# NetTieLibSample.net
KiCad netlist of a schematic drawn in Altium Designer
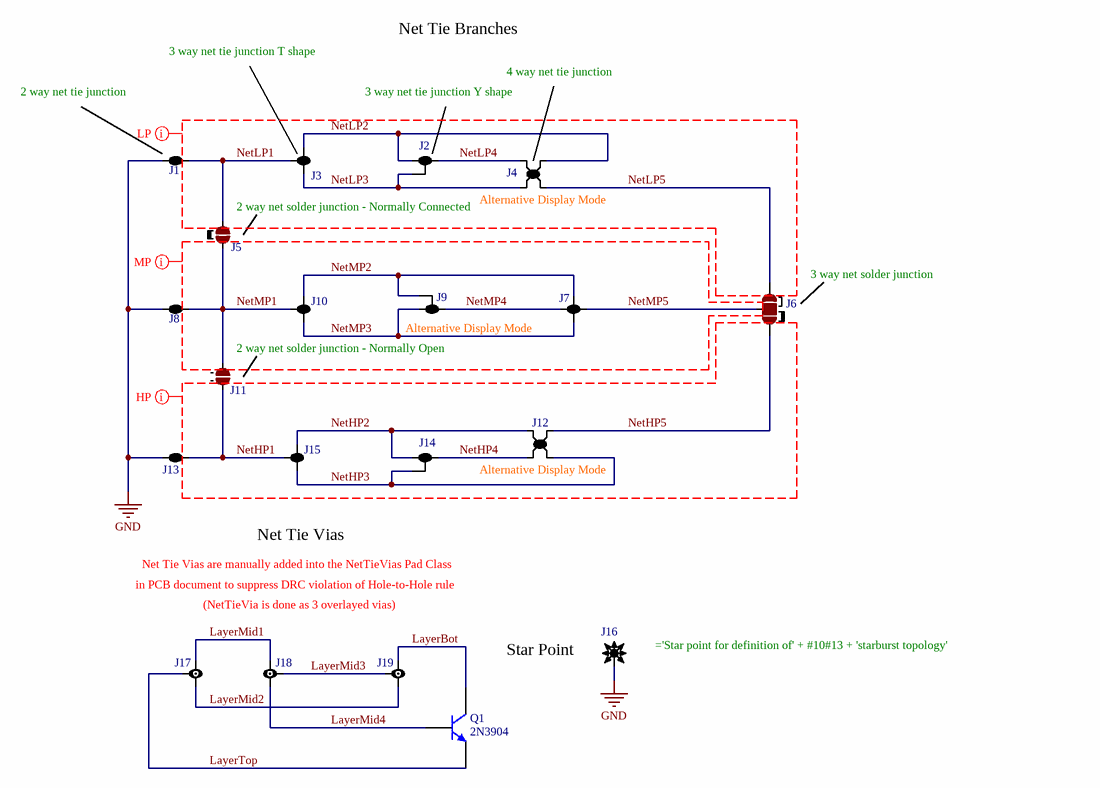
[diagram p0: NetTieLibSample.SchDoc]

(export (version "E")
  (design (tool "Eeschema 10.0.6"))
  (components
    (comp (ref "J1")
      (value "2 way net tie junction")
      (footprint "2way_LP")
      (libsource (lib "NetTieLib") (part "2way"))
    )
    (comp (ref "J2")
      (value "3 way net tie junction Y shape")
      (footprint "3wayY_LP")
      (libsource (lib "NetTieLib") (part "3wayY"))
    )
    (comp (ref "J3")
      (value "3 way net tie junction T shape")
      (footprint "3wayT_LP")
      (libsource (lib "NetTieLib") (part "3wayT"))
    )
    (comp (ref "J4")
      (value "4 way net tie junction")
      (footprint "4way_LP")
      (libsource (lib "NetTieLib") (part "4way"))
    )
    (comp (ref "J5")
      (value "2 way net solder junction - Normally Connected")
      (footprint "2waySolder_NC")
      (libsource (lib "NetTieLib") (part "2waySolderNC"))
    )
    (comp (ref "J6")
      (value "3 way net solder junction")
      (footprint "3waySolder")
      (libsource (lib "NetTieLib") (part "3waySolder"))
    )
    (comp (ref "J7")
      (value "4 way net tie junction")
      (footprint "4way_MP")
      (libsource (lib "") (part "4way_1"))
    )
    (comp (ref "J8")
      (value "2 way net tie junction")
      (footprint "2way_MP")
      (libsource (lib "NetTieLib") (part "2way"))
    )
    (comp (ref "J9")
      (value "3 way net tie junction Y shape")
      (footprint "3wayY_MP")
      (libsource (lib "") (part "3wayY_1"))
    )
    (comp (ref "J10")
      (value "3 way net tie junction T shape")
      (footprint "3wayT_MP")
      (libsource (lib "NetTieLib") (part "3wayT"))
    )
    (comp (ref "J11")
      (value "2 way net solder junction - Normally Open")
      (footprint "2waySolder_NO")
      (libsource (lib "NetTieLib") (part "2waySolderNO"))
    )
    (comp (ref "J12")
      (value "4 way net tie junction")
      (footprint "4way_HP")
      (libsource (lib "NetTieLib") (part "4way"))
    )
    (comp (ref "J13")
      (value "2 way net tie junction")
      (footprint "2way_HP")
      (libsource (lib "NetTieLib") (part "2way"))
    )
    (comp (ref "J14")
      (value "3 way net tie junction Y shape")
      (footprint "3wayY_HP")
      (libsource (lib "NetTieLib") (part "3wayY"))
    )
    (comp (ref "J15")
      (value "3 way net tie junction T shape")
      (footprint "3wayT_HP")
      (libsource (lib "NetTieLib") (part "3wayT"))
    )
    (comp (ref "J16")
      (value "Star point for definition ofstarburst topology")
      (footprint "StarPoint")
      (description "Star point for definition of starburst topology")
      (libsource (lib "NetTieLib") (part "StarPoint"))
    )
    (comp (ref "J17")
      (value "Net Tie Via")
      (footprint "NetTieVia03")
      (libsource (lib "NetTieLib") (part "NetTieVia"))
    )
    (comp (ref "J18")
      (value "Net Tie Via")
      (footprint "NetTieVia06")
      (libsource (lib "") (part "NetTieVia_1"))
    )
    (comp (ref "J19")
      (value "Net Tie Via")
      (footprint "NetTieVia08")
      (libsource (lib "NetTieLib") (part "NetTieVia"))
    )
    (comp (ref "Q1")
      (value "2N3904")
      (footprint "TO-92A")
      (description "NPN General Purpose Amplifier")
      (fields (field (name "PUBLISHER") "Altium Limited"))
      (libsource (lib "Miscellaneous Devices") (part "2N3904"))
    )
  )
  (nets
    (net (code "1") (name "/LayerBot") (class "Default")
      (node (ref "J19") (pin "2") (pinfunction "2_2") (pintype "passive"))
      (node (ref "Q1") (pin "3") (pinfunction "C_3") (pintype "passive"))
    )
    (net (code "2") (name "/LayerMid1") (class "Default")
      (node (ref "J17") (pin "2") (pinfunction "2_2") (pintype "passive"))
      (node (ref "J18") (pin "2") (pinfunction "2_2") (pintype "passive"))
    )
    (net (code "3") (name "/LayerMid2") (class "Default")
      (node (ref "J17") (pin "3") (pinfunction "3_3") (pintype "passive"))
      (node (ref "J19") (pin "3") (pinfunction "3_3") (pintype "passive"))
    )
    (net (code "4") (name "/LayerMid3") (class "Default")
      (node (ref "J18") (pin "1") (pinfunction "1_1") (pintype "passive"))
      (node (ref "J19") (pin "1") (pinfunction "1_1") (pintype "passive"))
    )
    (net (code "5") (name "/LayerMid4") (class "Default")
      (node (ref "J18") (pin "3") (pinfunction "3_3") (pintype "passive"))
      (node (ref "Q1") (pin "2") (pinfunction "B_2") (pintype "passive"))
    )
    (net (code "6") (name "/LayerTop") (class "Default")
      (node (ref "J17") (pin "1") (pinfunction "1_1") (pintype "passive"))
      (node (ref "Q1") (pin "1") (pinfunction "E_1") (pintype "passive"))
    )
    (net (code "7") (name "/NetHP1") (class "Default")
      (node (ref "J11") (pin "2") (pinfunction "2_2") (pintype "passive"))
      (node (ref "J13") (pin "2") (pinfunction "2_2") (pintype "passive"))
      (node (ref "J15") (pin "1") (pinfunction "1_1") (pintype "passive"))
    )
    (net (code "8") (name "/NetHP2") (class "Default")
      (node (ref "J12") (pin "2") (pinfunction "2_2") (pintype "passive"))
      (node (ref "J14") (pin "3") (pinfunction "3_3") (pintype "passive"))
      (node (ref "J15") (pin "2") (pinfunction "2_2") (pintype "passive"))
    )
    (net (code "9") (name "/NetHP3") (class "Default")
      (node (ref "J12") (pin "3") (pinfunction "3_3") (pintype "passive"))
      (node (ref "J14") (pin "2") (pinfunction "2_2") (pintype "passive"))
      (node (ref "J15") (pin "3") (pinfunction "3_3") (pintype "passive"))
    )
    (net (code "10") (name "/NetHP4") (class "Default")
      (node (ref "J12") (pin "1") (pinfunction "1_1") (pintype "passive"))
      (node (ref "J14") (pin "1") (pinfunction "1_1") (pintype "passive"))
    )
    (net (code "11") (name "/NetHP5") (class "Default")
      (node (ref "J12") (pin "4") (pinfunction "4_4") (pintype "passive"))
      (node (ref "J6") (pin "1") (pinfunction "1_1") (pintype "passive"))
    )
    (net (code "12") (name "/NetLP1") (class "Default")
      (node (ref "J1") (pin "2") (pinfunction "2_2") (pintype "passive"))
      (node (ref "J3") (pin "1") (pinfunction "1_1") (pintype "passive"))
      (node (ref "J5") (pin "1") (pinfunction "1_1") (pintype "passive"))
    )
    (net (code "13") (name "/NetLP2") (class "Default")
      (node (ref "J2") (pin "3") (pinfunction "3_3") (pintype "passive"))
      (node (ref "J3") (pin "2") (pinfunction "2_2") (pintype "passive"))
      (node (ref "J4") (pin "4") (pinfunction "4_4") (pintype "passive"))
    )
    (net (code "14") (name "/NetLP3") (class "Default")
      (node (ref "J2") (pin "2") (pinfunction "2_2") (pintype "passive"))
      (node (ref "J3") (pin "3") (pinfunction "3_3") (pintype "passive"))
      (node (ref "J4") (pin "1") (pinfunction "1_1") (pintype "passive"))
    )
    (net (code "15") (name "/NetLP4") (class "Default")
      (node (ref "J2") (pin "1") (pinfunction "1_1") (pintype "passive"))
      (node (ref "J4") (pin "2") (pinfunction "2_2") (pintype "passive"))
    )
    (net (code "16") (name "/NetLP5") (class "Default")
      (node (ref "J4") (pin "3") (pinfunction "3_3") (pintype "passive"))
      (node (ref "J6") (pin "3") (pinfunction "3_3") (pintype "passive"))
    )
    (net (code "17") (name "/NetMP1") (class "Default")
      (node (ref "J10") (pin "1") (pinfunction "1_1") (pintype "passive"))
      (node (ref "J11") (pin "1") (pinfunction "1_1") (pintype "passive"))
      (node (ref "J5") (pin "2") (pinfunction "2_2") (pintype "passive"))
      (node (ref "J8") (pin "2") (pinfunction "2_2") (pintype "passive"))
    )
    (net (code "18") (name "/NetMP2") (class "Default")
      (node (ref "J10") (pin "2") (pinfunction "2_2") (pintype "passive"))
      (node (ref "J7") (pin "2") (pinfunction "2_2") (pintype "passive"))
      (node (ref "J9") (pin "3") (pinfunction "3_3") (pintype "passive"))
    )
    (net (code "19") (name "/NetMP3") (class "Default")
      (node (ref "J10") (pin "3") (pinfunction "3_3") (pintype "passive"))
      (node (ref "J7") (pin "3") (pinfunction "3_3") (pintype "passive"))
      (node (ref "J9") (pin "2") (pinfunction "2_2") (pintype "passive"))
    )
    (net (code "20") (name "/NetMP4") (class "Default")
      (node (ref "J7") (pin "1") (pinfunction "1_1") (pintype "passive"))
      (node (ref "J9") (pin "1") (pinfunction "1_1") (pintype "passive"))
    )
    (net (code "21") (name "/NetMP5") (class "Default")
      (node (ref "J6") (pin "2") (pinfunction "2_2") (pintype "passive"))
      (node (ref "J7") (pin "4") (pinfunction "4_4") (pintype "passive"))
    )
    (net (code "22") (name "GND") (class "Default")
      (node (ref "J1") (pin "1") (pinfunction "1_1") (pintype "passive"))
      (node (ref "J13") (pin "1") (pinfunction "1_1") (pintype "passive"))
      (node (ref "J16") (pin "1") (pinfunction "1_1") (pintype "passive"))
      (node (ref "J8") (pin "1") (pinfunction "1_1") (pintype "passive"))
    )
  )
)
